# Connectors.net
KiCad netlist of a schematic drawn in Altium Designer
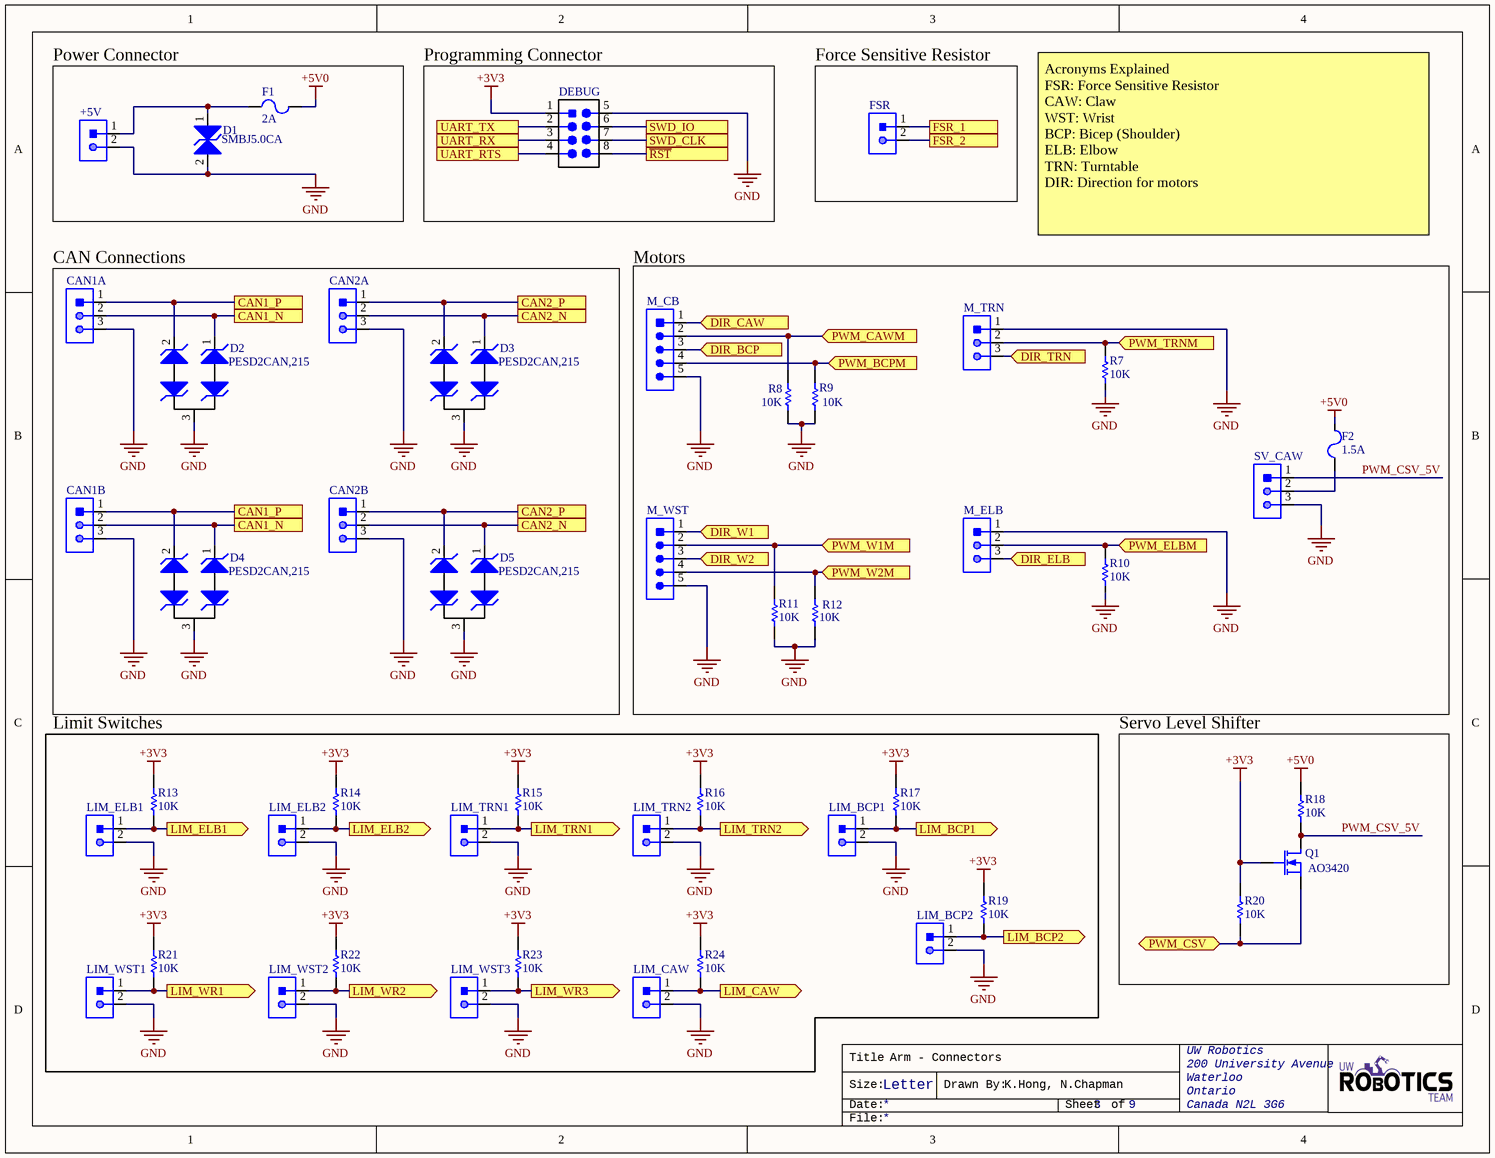
[diagram p0: Connectors.SchDoc]

(export (version "E")
  (design (tool "Eeschema 10.0.6"))
  (components
    (comp (ref "+5V")
      (value "CON_2M_SM4")
      (footprint "JST-B2B-SM4-TB")
      (description "CONN HEADER SMD 2POS 2MM")
      (fields
        (field (name "MANUFACTURER") "JST")
        (field (name "MANUFACTURER PART NUMBER") "B2B-PH-SM4-TB(LF)(SN)")
      )
      (libsource (lib "UWRT_Schematic_Library_2020") (part "CON_2M_SM4"))
    )
    (comp (ref "CAN1A")
      (value "CON_3M_SM4")
      (footprint "JST-B3B-SM4-TB")
      (description "CONN HEADER SMD 3POS 2MM")
      (fields
        (field (name "MANUFACTURER") "JST")
        (field (name "MANUFACTURER PART NUMBER") "B3B-PH-SM4-TB(LF)(SN)")
      )
      (libsource (lib "UWRT_Schematic_Library_2020") (part "CON_3M_SM4"))
    )
    (comp (ref "CAN1B")
      (value "CON_3M_SM4")
      (footprint "JST-B3B-SM4-TB")
      (description "CONN HEADER SMD 3POS 2MM")
      (fields
        (field (name "MANUFACTURER") "JST")
        (field (name "MANUFACTURER PART NUMBER") "B3B-PH-SM4-TB(LF)(SN)")
      )
      (libsource (lib "UWRT_Schematic_Library_2020") (part "CON_3M_SM4"))
    )
    (comp (ref "CAN2A")
      (value "CON_3M_SM4")
      (footprint "JST-B3B-SM4-TB")
      (description "CONN HEADER SMD 3POS 2MM")
      (fields
        (field (name "MANUFACTURER") "JST")
        (field (name "MANUFACTURER PART NUMBER") "B3B-PH-SM4-TB(LF)(SN)")
      )
      (libsource (lib "UWRT_Schematic_Library_2020") (part "CON_3M_SM4"))
    )
    (comp (ref "CAN2B")
      (value "CON_3M_SM4")
      (footprint "JST-B3B-SM4-TB")
      (description "CONN HEADER SMD 3POS 2MM")
      (fields
        (field (name "MANUFACTURER") "JST")
        (field (name "MANUFACTURER PART NUMBER") "B3B-PH-SM4-TB(LF)(SN)")
      )
      (libsource (lib "UWRT_Schematic_Library_2020") (part "CON_3M_SM4"))
    )
    (comp (ref "D1")
      (value "TVS_DIODE_BIDIRECTIONAL")
      (footprint "TVS_DIODE_BIDIRECTIONAL")
      (description "TVS DIODE 5V 9.2V DO214AA")
      (fields (field (name "MANUFACTURER PART NUMBER 1") "SMBJ5.0CA"))
      (libsource (lib "UWRT_Schematic_Library_2020") (part "TVS_DIODE_BIDIRECTIONAL"))
    )
    (comp (ref "D2")
      (value "TVS_DIODE_CAN")
      (footprint "NXP-SOT323-3")
      (description "TVS DIODE 24V 41V SOT323-3")
      (fields
        (field (name "MANUFACTURER") "Nexperia USA Inc.")
        (field (name "MANUFACTURER PART NUMBER") "PESD2CAN,215")
      )
      (libsource (lib "UWRT_Schematic_Library_2020") (part "TVS_DIODE_CAN"))
    )
    (comp (ref "D3")
      (value "TVS_DIODE_CAN")
      (footprint "NXP-SOT323-3")
      (description "TVS DIODE 24V 41V SOT323-3")
      (fields
        (field (name "MANUFACTURER") "Nexperia USA Inc.")
        (field (name "MANUFACTURER PART NUMBER") "PESD2CAN,215")
      )
      (libsource (lib "UWRT_Schematic_Library_2020") (part "TVS_DIODE_CAN"))
    )
    (comp (ref "D4")
      (value "TVS_DIODE_CAN")
      (footprint "NXP-SOT323-3")
      (description "TVS DIODE 24V 41V SOT323-3")
      (fields
        (field (name "MANUFACTURER") "Nexperia USA Inc.")
        (field (name "MANUFACTURER PART NUMBER") "PESD2CAN,215")
      )
      (libsource (lib "UWRT_Schematic_Library_2020") (part "TVS_DIODE_CAN"))
    )
    (comp (ref "D5")
      (value "TVS_DIODE_CAN")
      (footprint "NXP-SOT323-3")
      (description "TVS DIODE 24V 41V SOT323-3")
      (fields
        (field (name "MANUFACTURER") "Nexperia USA Inc.")
        (field (name "MANUFACTURER PART NUMBER") "PESD2CAN,215")
      )
      (libsource (lib "UWRT_Schematic_Library_2020") (part "TVS_DIODE_CAN"))
    )
    (comp (ref "DEBUG")
      (value "HEADER 4X2")
      (footprint "HEADER_2X4")
      (description "CONN HEADER VERT 8POS 2.54MM")
      (libsource (lib "UWRT_Schematic_Library_2020") (part "HEADER 4X2"))
    )
    (comp (ref "F1")
      (value "FUSE_2A_0603")
      (footprint "FUSE_0603")
      (description "FUSE SMD 2A 32V")
      (fields (field (name "CURRENT RATING") "2A"))
      (libsource (lib "UWRT_Schematic_Library_2020") (part "FUSE_2A_0603"))
    )
    (comp (ref "F2")
      (value "FUSE_1.5A_0603")
      (footprint "FUSE_0603")
      (description "FUSE SMD 1.5A 32V")
      (fields (field (name "CURRENT RATING") "1.5A"))
      (libsource (lib "UWRT_Schematic_Library_2020") (part "FUSE_1.5A_0603"))
    )
    (comp (ref "FSR")
      (value "CON_2M_SM4")
      (footprint "JST-B2B-SM4-TB")
      (description "CONN HEADER SMD 2POS 2MM")
      (fields
        (field (name "MANUFACTURER") "JST")
        (field (name "MANUFACTURER PART NUMBER") "B2B-PH-SM4-TB(LF)(SN)")
      )
      (libsource (lib "UWRT_Schematic_Library_2020") (part "CON_2M_SM4"))
    )
    (comp (ref "LIM_BCP1")
      (value "CON_2M_SM4")
      (footprint "JST-B2B-SM4-TB")
      (description "CONN HEADER SMD 2POS 2MM")
      (fields
        (field (name "MANUFACTURER") "JST")
        (field (name "MANUFACTURER PART NUMBER") "B2B-PH-SM4-TB(LF)(SN)")
      )
      (libsource (lib "UWRT_Schematic_Library_2020") (part "CON_2M_SM4"))
    )
    (comp (ref "LIM_BCP2")
      (value "CON_2M_SM4")
      (footprint "JST-B2B-SM4-TB")
      (description "CONN HEADER SMD 2POS 2MM")
      (fields
        (field (name "MANUFACTURER") "JST")
        (field (name "MANUFACTURER PART NUMBER") "B2B-PH-SM4-TB(LF)(SN)")
      )
      (libsource (lib "UWRT_Schematic_Library_2020") (part "CON_2M_SM4"))
    )
    (comp (ref "LIM_CAW")
      (value "CON_2M_SM4")
      (footprint "JST-B2B-SM4-TB")
      (description "CONN HEADER SMD 2POS 2MM")
      (fields
        (field (name "MANUFACTURER") "JST")
        (field (name "MANUFACTURER PART NUMBER") "B2B-PH-SM4-TB(LF)(SN)")
      )
      (libsource (lib "UWRT_Schematic_Library_2020") (part "CON_2M_SM4"))
    )
    (comp (ref "LIM_ELB1")
      (value "CON_2M_SM4")
      (footprint "JST-B2B-SM4-TB")
      (description "CONN HEADER SMD 2POS 2MM")
      (fields
        (field (name "MANUFACTURER") "JST")
        (field (name "MANUFACTURER PART NUMBER") "B2B-PH-SM4-TB(LF)(SN)")
      )
      (libsource (lib "UWRT_Schematic_Library_2020") (part "CON_2M_SM4"))
    )
    (comp (ref "LIM_ELB2")
      (value "CON_2M_SM4")
      (footprint "JST-B2B-SM4-TB")
      (description "CONN HEADER SMD 2POS 2MM")
      (fields
        (field (name "MANUFACTURER") "JST")
        (field (name "MANUFACTURER PART NUMBER") "B2B-PH-SM4-TB(LF)(SN)")
      )
      (libsource (lib "UWRT_Schematic_Library_2020") (part "CON_2M_SM4"))
    )
    (comp (ref "LIM_TRN1")
      (value "CON_2M_SM4")
      (footprint "JST-B2B-SM4-TB")
      (description "CONN HEADER SMD 2POS 2MM")
      (fields
        (field (name "MANUFACTURER") "JST")
        (field (name "MANUFACTURER PART NUMBER") "B2B-PH-SM4-TB(LF)(SN)")
      )
      (libsource (lib "UWRT_Schematic_Library_2020") (part "CON_2M_SM4"))
    )
    (comp (ref "LIM_TRN2")
      (value "CON_2M_SM4")
      (footprint "JST-B2B-SM4-TB")
      (description "CONN HEADER SMD 2POS 2MM")
      (fields
        (field (name "MANUFACTURER") "JST")
        (field (name "MANUFACTURER PART NUMBER") "B2B-PH-SM4-TB(LF)(SN)")
      )
      (libsource (lib "UWRT_Schematic_Library_2020") (part "CON_2M_SM4"))
    )
    (comp (ref "LIM_WST1")
      (value "CON_2M_SM4")
      (footprint "JST-B2B-SM4-TB")
      (description "CONN HEADER SMD 2POS 2MM")
      (fields
        (field (name "MANUFACTURER") "JST")
        (field (name "MANUFACTURER PART NUMBER") "B2B-PH-SM4-TB(LF)(SN)")
      )
      (libsource (lib "UWRT_Schematic_Library_2020") (part "CON_2M_SM4"))
    )
    (comp (ref "LIM_WST2")
      (value "CON_2M_SM4")
      (footprint "JST-B2B-SM4-TB")
      (description "CONN HEADER SMD 2POS 2MM")
      (fields
        (field (name "MANUFACTURER") "JST")
        (field (name "MANUFACTURER PART NUMBER") "B2B-PH-SM4-TB(LF)(SN)")
      )
      (libsource (lib "UWRT_Schematic_Library_2020") (part "CON_2M_SM4"))
    )
    (comp (ref "LIM_WST3")
      (value "CON_2M_SM4")
      (footprint "JST-B2B-SM4-TB")
      (description "CONN HEADER SMD 2POS 2MM")
      (fields
        (field (name "MANUFACTURER") "JST")
        (field (name "MANUFACTURER PART NUMBER") "B2B-PH-SM4-TB(LF)(SN)")
      )
      (libsource (lib "UWRT_Schematic_Library_2020") (part "CON_2M_SM4"))
    )
    (comp (ref "M_CB")
      (value "CON_5M_SM4")
      (footprint "JST-B5B-SM4-TB")
      (description "CONN HEADER SMD 5POS 2MM")
      (fields
        (field (name "MANUFACTURER") "JST")
        (field (name "MANUFACTURER PART NUMBER") "B5B-PH-SM4-TB(LF)(SN)")
      )
      (libsource (lib "UWRT_Schematic_Library_2020") (part "CON_5M_SM4"))
    )
    (comp (ref "M_ELB")
      (value "CON_3M_SM4")
      (footprint "JST-B3B-SM4-TB")
      (description "CONN HEADER SMD 3POS 2MM")
      (fields
        (field (name "MANUFACTURER") "JST")
        (field (name "MANUFACTURER PART NUMBER") "B3B-PH-SM4-TB(LF)(SN)")
      )
      (libsource (lib "UWRT_Schematic_Library_2020") (part "CON_3M_SM4"))
    )
    (comp (ref "M_TRN")
      (value "CON_3M_SM4")
      (footprint "JST-B3B-SM4-TB")
      (description "CONN HEADER SMD 3POS 2MM")
      (fields
        (field (name "MANUFACTURER") "JST")
        (field (name "MANUFACTURER PART NUMBER") "B3B-PH-SM4-TB(LF)(SN)")
      )
      (libsource (lib "UWRT_Schematic_Library_2020") (part "CON_3M_SM4"))
    )
    (comp (ref "M_WST")
      (value "CON_5M_SM4")
      (footprint "JST-B5B-SM4-TB")
      (description "CONN HEADER SMD 5POS 2MM")
      (fields
        (field (name "MANUFACTURER") "JST")
        (field (name "MANUFACTURER PART NUMBER") "B5B-PH-SM4-TB(LF)(SN)")
      )
      (libsource (lib "UWRT_Schematic_Library_2020") (part "CON_5M_SM4"))
    )
    (comp (ref "Q1")
      (value "NMOS_20V_6A")
      (footprint "NMOS_SOT23-3")
      (description "MOSFET N-CH 20V 6A SOT23")
      (fields (field (name "MPN") "AO3420") (field (name "MANUFACTURER") "Alpha & Omega"))
      (libsource (lib "UWRT_Schematic_Library_2020") (part "NMOS_20V_6A"))
    )
    (comp (ref "R7")
      (value "10K")
      (footprint "RESC0603(1608)_N")
      (description "RES SMD 10K OHM 5% 1/10W 0603")
      (fields (field (name "MANUFACTURER") "Yageo") (field (name "MPN") "RC0603JR-0710KL"))
      (libsource (lib "UWRT_Schematic_Library_2020") (part "RES_10K_0603"))
    )
    (comp (ref "R8")
      (value "10K")
      (footprint "RESC0603(1608)_N")
      (description "RES SMD 10K OHM 5% 1/10W 0603")
      (fields (field (name "MANUFACTURER") "Yageo") (field (name "MPN") "RC0603JR-0710KL"))
      (libsource (lib "UWRT_Schematic_Library_2020") (part "RES_10K_0603"))
    )
    (comp (ref "R9")
      (value "10K")
      (footprint "RESC0603(1608)_N")
      (description "RES SMD 10K OHM 5% 1/10W 0603")
      (fields (field (name "MANUFACTURER") "Yageo") (field (name "MPN") "RC0603JR-0710KL"))
      (libsource (lib "UWRT_Schematic_Library_2020") (part "RES_10K_0603"))
    )
    (comp (ref "R10")
      (value "10K")
      (footprint "RESC0603(1608)_N")
      (description "RES SMD 10K OHM 5% 1/10W 0603")
      (fields (field (name "MANUFACTURER") "Yageo") (field (name "MPN") "RC0603JR-0710KL"))
      (libsource (lib "UWRT_Schematic_Library_2020") (part "RES_10K_0603"))
    )
    (comp (ref "R11")
      (value "10K")
      (footprint "RESC0603(1608)_N")
      (description "RES SMD 10K OHM 5% 1/10W 0603")
      (fields (field (name "MANUFACTURER") "Yageo") (field (name "MPN") "RC0603JR-0710KL"))
      (libsource (lib "UWRT_Schematic_Library_2020") (part "RES_10K_0603"))
    )
    (comp (ref "R12")
      (value "10K")
      (footprint "RESC0603(1608)_N")
      (description "RES SMD 10K OHM 5% 1/10W 0603")
      (fields (field (name "MANUFACTURER") "Yageo") (field (name "MPN") "RC0603JR-0710KL"))
      (libsource (lib "UWRT_Schematic_Library_2020") (part "RES_10K_0603"))
    )
    (comp (ref "R13")
      (value "10K")
      (footprint "RESC0603(1608)_N")
      (description "RES SMD 10K OHM 5% 1/10W 0603")
      (fields (field (name "MANUFACTURER") "Yageo") (field (name "MPN") "RC0603JR-0710KL"))
      (libsource (lib "UWRT_Schematic_Library_2020") (part "RES_10K_0603"))
    )
    (comp (ref "R14")
      (value "10K")
      (footprint "RESC0603(1608)_N")
      (description "RES SMD 10K OHM 5% 1/10W 0603")
      (fields (field (name "MANUFACTURER") "Yageo") (field (name "MPN") "RC0603JR-0710KL"))
      (libsource (lib "UWRT_Schematic_Library_2020") (part "RES_10K_0603"))
    )
    (comp (ref "R15")
      (value "10K")
      (footprint "RESC0603(1608)_N")
      (description "RES SMD 10K OHM 5% 1/10W 0603")
      (fields (field (name "MANUFACTURER") "Yageo") (field (name "MPN") "RC0603JR-0710KL"))
      (libsource (lib "UWRT_Schematic_Library_2020") (part "RES_10K_0603"))
    )
    (comp (ref "R16")
      (value "10K")
      (footprint "RESC0603(1608)_N")
      (description "RES SMD 10K OHM 5% 1/10W 0603")
      (fields (field (name "MANUFACTURER") "Yageo") (field (name "MPN") "RC0603JR-0710KL"))
      (libsource (lib "UWRT_Schematic_Library_2020") (part "RES_10K_0603"))
    )
    (comp (ref "R17")
      (value "10K")
      (footprint "RESC0603(1608)_N")
      (description "RES SMD 10K OHM 5% 1/10W 0603")
      (fields (field (name "MANUFACTURER") "Yageo") (field (name "MPN") "RC0603JR-0710KL"))
      (libsource (lib "UWRT_Schematic_Library_2020") (part "RES_10K_0603"))
    )
    (comp (ref "R18")
      (value "10K")
      (footprint "RESC0603(1608)_N")
      (description "RES SMD 10K OHM 5% 1/10W 0603")
      (fields (field (name "MANUFACTURER") "Yageo") (field (name "MPN") "RC0603JR-0710KL"))
      (libsource (lib "UWRT_Schematic_Library_2020") (part "RES_10K_0603"))
    )
    (comp (ref "R19")
      (value "10K")
      (footprint "RESC0603(1608)_N")
      (description "RES SMD 10K OHM 5% 1/10W 0603")
      (fields (field (name "MANUFACTURER") "Yageo") (field (name "MPN") "RC0603JR-0710KL"))
      (libsource (lib "UWRT_Schematic_Library_2020") (part "RES_10K_0603"))
    )
    (comp (ref "R20")
      (value "10K")
      (footprint "RESC0603(1608)_N")
      (description "RES SMD 10K OHM 5% 1/10W 0603")
      (fields (field (name "MANUFACTURER") "Yageo") (field (name "MPN") "RC0603JR-0710KL"))
      (libsource (lib "UWRT_Schematic_Library_2020") (part "RES_10K_0603"))
    )
    (comp (ref "R21")
      (value "10K")
      (footprint "RESC0603(1608)_N")
      (description "RES SMD 10K OHM 5% 1/10W 0603")
      (fields (field (name "MANUFACTURER") "Yageo") (field (name "MPN") "RC0603JR-0710KL"))
      (libsource (lib "UWRT_Schematic_Library_2020") (part "RES_10K_0603"))
    )
    (comp (ref "R22")
      (value "10K")
      (footprint "RESC0603(1608)_N")
      (description "RES SMD 10K OHM 5% 1/10W 0603")
      (fields (field (name "MANUFACTURER") "Yageo") (field (name "MPN") "RC0603JR-0710KL"))
      (libsource (lib "UWRT_Schematic_Library_2020") (part "RES_10K_0603"))
    )
    (comp (ref "R23")
      (value "10K")
      (footprint "RESC0603(1608)_N")
      (description "RES SMD 10K OHM 5% 1/10W 0603")
      (fields (field (name "MANUFACTURER") "Yageo") (field (name "MPN") "RC0603JR-0710KL"))
      (libsource (lib "UWRT_Schematic_Library_2020") (part "RES_10K_0603"))
    )
    (comp (ref "R24")
      (value "10K")
      (footprint "RESC0603(1608)_N")
      (description "RES SMD 10K OHM 5% 1/10W 0603")
      (fields (field (name "MANUFACTURER") "Yageo") (field (name "MPN") "RC0603JR-0710KL"))
      (libsource (lib "UWRT_Schematic_Library_2020") (part "RES_10K_0603"))
    )
    (comp (ref "SV_CAW")
      (value "CON_3M_SM4")
      (footprint "JST-B3B-SM4-TB")
      (description "CONN HEADER SMD 3POS 2MM")
      (fields
        (field (name "MANUFACTURER") "JST")
        (field (name "MANUFACTURER PART NUMBER") "B3B-PH-SM4-TB(LF)(SN)")
      )
      (libsource (lib "UWRT_Schematic_Library_2020") (part "CON_3M_SM4"))
    )
  )
  (nets
    (net (code "1") (name "+3V3") (class "Default")
      (node (ref "DEBUG") (pin "1") (pinfunction "VCC_1") (pintype "passive"))
      (node (ref "Q1") (pin "1") (pinfunction "G_1") (pintype "passive"))
      (node (ref "R13") (pin "2") (pinfunction "2_2") (pintype "passive"))
      (node (ref "R14") (pin "2") (pinfunction "2_2") (pintype "passive"))
      (node (ref "R15") (pin "2") (pinfunction "2_2") (pintype "passive"))
      (node (ref "R16") (pin "2") (pinfunction "2_2") (pintype "passive"))
      (node (ref "R17") (pin "2") (pinfunction "2_2") (pintype "passive"))
      (node (ref "R19") (pin "2") (pinfunction "2_2") (pintype "passive"))
      (node (ref "R20") (pin "2") (pinfunction "2_2") (pintype "passive"))
      (node (ref "R21") (pin "2") (pinfunction "2_2") (pintype "passive"))
      (node (ref "R22") (pin "2") (pinfunction "2_2") (pintype "passive"))
      (node (ref "R23") (pin "2") (pinfunction "2_2") (pintype "passive"))
      (node (ref "R24") (pin "2") (pinfunction "2_2") (pintype "passive"))
    )
    (net (code "2") (name "+5V0") (class "Default")
      (node (ref "F1") (pin "2") (pinfunction "2_2") (pintype "passive"))
      (node (ref "F2") (pin "2") (pinfunction "2_2") (pintype "passive"))
      (node (ref "R18") (pin "2") (pinfunction "2_2") (pintype "passive"))
    )
    (net (code "3") (name "/CAN1_N") (class "Default")
      (node (ref "CAN1A") (pin "2") (pinfunction "2_2") (pintype "passive"))
      (node (ref "CAN1B") (pin "2") (pinfunction "2_2") (pintype "passive"))
      (node (ref "D2") (pin "1") (pinfunction "1_1") (pintype "passive"))
      (node (ref "D4") (pin "1") (pinfunction "1_1") (pintype "passive"))
    )
    (net (code "4") (name "/CAN1_P") (class "Default")
      (node (ref "CAN1A") (pin "1") (pinfunction "1_1") (pintype "passive"))
      (node (ref "CAN1B") (pin "1") (pinfunction "1_1") (pintype "passive"))
      (node (ref "D2") (pin "2") (pinfunction "2_2") (pintype "passive"))
      (node (ref "D4") (pin "2") (pinfunction "2_2") (pintype "passive"))
    )
    (net (code "5") (name "/CAN2_N") (class "Default")
      (node (ref "CAN2A") (pin "2") (pinfunction "2_2") (pintype "passive"))
      (node (ref "CAN2B") (pin "2") (pinfunction "2_2") (pintype "passive"))
      (node (ref "D3") (pin "1") (pinfunction "1_1") (pintype "passive"))
      (node (ref "D5") (pin "1") (pinfunction "1_1") (pintype "passive"))
    )
    (net (code "6") (name "/CAN2_P") (class "Default")
      (node (ref "CAN2A") (pin "1") (pinfunction "1_1") (pintype "passive"))
      (node (ref "CAN2B") (pin "1") (pinfunction "1_1") (pintype "passive"))
      (node (ref "D3") (pin "2") (pinfunction "2_2") (pintype "passive"))
      (node (ref "D5") (pin "2") (pinfunction "2_2") (pintype "passive"))
    )
    (net (code "7") (name "/DIR_BCP") (class "Default")
      (node (ref "M_CB") (pin "3") (pinfunction "3_3") (pintype "passive"))
    )
    (net (code "8") (name "/DIR_CAW") (class "Default")
      (node (ref "M_CB") (pin "1") (pinfunction "1_1") (pintype "passive"))
    )
    (net (code "9") (name "/DIR_ELB") (class "Default")
      (node (ref "M_ELB") (pin "3") (pinfunction "3_3") (pintype "passive"))
    )
    (net (code "10") (name "/DIR_TRN") (class "Default")
      (node (ref "M_TRN") (pin "3") (pinfunction "3_3") (pintype "passive"))
    )
    (net (code "11") (name "/DIR_W1") (class "Default")
      (node (ref "M_WST") (pin "1") (pinfunction "1_1") (pintype "passive"))
    )
    (net (code "12") (name "/DIR_W2") (class "Default")
      (node (ref "M_WST") (pin "3") (pinfunction "3_3") (pintype "passive"))
    )
    (net (code "13") (name "/FSR_1") (class "Default")
      (node (ref "FSR") (pin "1") (pinfunction "1_1") (pintype "passive"))
    )
    (net (code "14") (name "/FSR_2") (class "Default")
      (node (ref "FSR") (pin "2") (pinfunction "2_2") (pintype "passive"))
    )
    (net (code "15") (name "/LIM_BCP1") (class "Default")
      (node (ref "LIM_BCP1") (pin "1") (pinfunction "1_1") (pintype "passive"))
      (node (ref "R17") (pin "1") (pinfunction "1_1") (pintype "passive"))
    )
    (net (code "16") (name "/LIM_BCP2") (class "Default")
      (node (ref "LIM_BCP2") (pin "1") (pinfunction "1_1") (pintype "passive"))
      (node (ref "R19") (pin "1") (pinfunction "1_1") (pintype "passive"))
    )
    (net (code "17") (name "/LIM_CAW") (class "Default")
      (node (ref "LIM_CAW") (pin "1") (pinfunction "1_1") (pintype "passive"))
      (node (ref "R24") (pin "1") (pinfunction "1_1") (pintype "passive"))
    )
    (net (code "18") (name "/LIM_ELB1") (class "Default")
      (node (ref "LIM_ELB1") (pin "1") (pinfunction "1_1") (pintype "passive"))
      (node (ref "R13") (pin "1") (pinfunction "1_1") (pintype "passive"))
    )
    (net (code "19") (name "/LIM_ELB2") (class "Default")
      (node (ref "LIM_ELB2") (pin "1") (pinfunction "1_1") (pintype "passive"))
      (node (ref "R14") (pin "1") (pinfunction "1_1") (pintype "passive"))
    )
    (net (code "20") (name "/LIM_TRN1") (class "Default")
      (node (ref "LIM_TRN1") (pin "1") (pinfunction "1_1") (pintype "passive"))
      (node (ref "R15") (pin "1") (pinfunction "1_1") (pintype "passive"))
    )
    (net (code "21") (name "/LIM_TRN2") (class "Default")
      (node (ref "LIM_TRN2") (pin "1") (pinfunction "1_1") (pintype "passive"))
      (node (ref "R16") (pin "1") (pinfunction "1_1") (pintype "passive"))
    )
    (net (code "22") (name "/LIM_WR1") (class "Default")
      (node (ref "LIM_WST1") (pin "1") (pinfunction "1_1") (pintype "passive"))
      (node (ref "R21") (pin "1") (pinfunction "1_1") (pintype "passive"))
    )
    (net (code "23") (name "/LIM_WR2") (class "Default")
      (node (ref "LIM_WST2") (pin "1") (pinfunction "1_1") (pintype "passive"))
      (node (ref "R22") (pin "1") (pinfunction "1_1") (pintype "passive"))
    )
    (net (code "24") (name "/LIM_WR3") (class "Default")
      (node (ref "LIM_WST3") (pin "1") (pinfunction "1_1") (pintype "passive"))
      (node (ref "R23") (pin "1") (pinfunction "1_1") (pintype "passive"))
    )
    (net (code "25") (name "/PWM_BCPM") (class "Default")
      (node (ref "M_CB") (pin "4") (pinfunction "4_4") (pintype "passive"))
      (node (ref "R9") (pin "2") (pinfunction "2_2") (pintype "passive"))
    )
    (net (code "26") (name "/PWM_CAWM") (class "Default")
      (node (ref "M_CB") (pin "2") (pinfunction "2_2") (pintype "passive"))
      (node (ref "R8") (pin "2") (pinfunction "2_2") (pintype "passive"))
    )
    (net (code "27") (name "/PWM_CSV") (class "Default")
      (node (ref "Q1") (pin "2") (pinfunction "S_2") (pintype "passive"))
      (node (ref "R20") (pin "1") (pinfunction "1_1") (pintype "passive"))
    )
    (net (code "28") (name "/PWM_CSV_5V") (class "Default")
      (node (ref "Q1") (pin "3") (pinfunction "D_3") (pintype "passive"))
      (node (ref "R18") (pin "1") (pinfunction "1_1") (pintype "passive"))
      (node (ref "SV_CAW") (pin "1") (pinfunction "1_1") (pintype "passive"))
    )
    (net (code "29") (name "/PWM_ELBM") (class "Default")
      (node (ref "M_ELB") (pin "2") (pinfunction "2_2") (pintype "passive"))
      (node (ref "R10") (pin "2") (pinfunction "2_2") (pintype "passive"))
    )
    (net (code "30") (name "/PWM_TRNM") (class "Default")
      (node (ref "M_TRN") (pin "2") (pinfunction "2_2") (pintype "passive"))
      (node (ref "R7") (pin "2") (pinfunction "2_2") (pintype "passive"))
    )
    (net (code "31") (name "/PWM_W1M") (class "Default")
      (node (ref "M_WST") (pin "2") (pinfunction "2_2") (pintype "passive"))
      (node (ref "R11") (pin "2") (pinfunction "2_2") (pintype "passive"))
    )
    (net (code "32") (name "/PWM_W2M") (class "Default")
      (node (ref "M_WST") (pin "4") (pinfunction "4_4") (pintype "passive"))
      (node (ref "R12") (pin "2") (pinfunction "2_2") (pintype "passive"))
    )
    (net (code "33") (name "/SWD_CLK") (class "Default")
      (node (ref "DEBUG") (pin "7") (pinfunction "3_7") (pintype "passive"))
    )
    (net (code "34") (name "/SWD_IO") (class "Default")
      (node (ref "DEBUG") (pin "6") (pinfunction "2_6") (pintype "passive"))
    )
    (net (code "35") (name "/UART_RTS") (class "Default")
      (node (ref "DEBUG") (pin "4") (pinfunction "4_4") (pintype "passive"))
    )
    (net (code "36") (name "/UART_RX") (class "Default")
      (node (ref "DEBUG") (pin "3") (pinfunction "3_3") (pintype "passive"))
    )
    (net (code "37") (name "/UART_TX") (class "Default")
      (node (ref "DEBUG") (pin "2") (pinfunction "2_2") (pintype "passive"))
    )
    (net (code "38") (name "/~{RST}") (class "Default")
      (node (ref "DEBUG") (pin "8") (pinfunction "4_8") (pintype "passive"))
    )
    (net (code "39") (name "GND") (class "Default")
      (node (ref "+5V") (pin "2") (pinfunction "2_2") (pintype "passive"))
      (node (ref "CAN1A") (pin "3") (pinfunction "3_3") (pintype "passive"))
      (node (ref "CAN1B") (pin "3") (pinfunction "3_3") (pintype "passive"))
      (node (ref "CAN2A") (pin "3") (pinfunction "3_3") (pintype "passive"))
      (node (ref "CAN2B") (pin "3") (pinfunction "3_3") (pintype "passive"))
      (node (ref "D1") (pin "2") (pinfunction "2_2") (pintype "passive"))
      (node (ref "D2") (pin "3") (pinfunction "3_3") (pintype "passive"))
      (node (ref "D3") (pin "3") (pinfunction "3_3") (pintype "passive"))
      (node (ref "D4") (pin "3") (pinfunction "3_3") (pintype "passive"))
      (node (ref "D5") (pin "3") (pinfunction "3_3") (pintype "passive"))
      (node (ref "DEBUG") (pin "5") (pinfunction "GND_5") (pintype "passive"))
      (node (ref "LIM_BCP1") (pin "2") (pinfunction "2_2") (pintype "passive"))
      (node (ref "LIM_BCP2") (pin "2") (pinfunction "2_2") (pintype "passive"))
      (node (ref "LIM_CAW") (pin "2") (pinfunction "2_2") (pintype "passive"))
      (node (ref "LIM_ELB1") (pin "2") (pinfunction "2_2") (pintype "passive"))
      (node (ref "LIM_ELB2") (pin "2") (pinfunction "2_2") (pintype "passive"))
      (node (ref "LIM_TRN1") (pin "2") (pinfunction "2_2") (pintype "passive"))
      (node (ref "LIM_TRN2") (pin "2") (pinfunction "2_2") (pintype "passive"))
      (node (ref "LIM_WST1") (pin "2") (pinfunction "2_2") (pintype "passive"))
      (node (ref "LIM_WST2") (pin "2") (pinfunction "2_2") (pintype "passive"))
      (node (ref "LIM_WST3") (pin "2") (pinfunction "2_2") (pintype "passive"))
      (node (ref "M_CB") (pin "5") (pinfunction "5_5") (pintype "passive"))
      (node (ref "M_ELB") (pin "1") (pinfunction "1_1") (pintype "passive"))
      (node (ref "M_TRN") (pin "1") (pinfunction "1_1") (pintype "passive"))
      (node (ref "M_WST") (pin "5") (pinfunction "5_5") (pintype "passive"))
      (node (ref "R10") (pin "1") (pinfunction "1_1") (pintype "passive"))
      (node (ref "R11") (pin "1") (pinfunction "1_1") (pintype "passive"))
      (node (ref "R12") (pin "1") (pinfunction "1_1") (pintype "passive"))
      (node (ref "R7") (pin "1") (pinfunction "1_1") (pintype "passive"))
      (node (ref "R8") (pin "1") (pinfunction "1_1") (pintype "passive"))
      (node (ref "R9") (pin "1") (pinfunction "1_1") (pintype "passive"))
      (node (ref "SV_CAW") (pin "3") (pinfunction "3_3") (pintype "passive"))
    )
    (net (code "40") (name "Net-(+5V-Pad1)") (class "Default")
      (node (ref "+5V") (pin "1") (pinfunction "1_1") (pintype "passive"))
      (node (ref "D1") (pin "1") (pinfunction "1_1") (pintype "passive"))
      (node (ref "F1") (pin "1") (pinfunction "1_1") (pintype "passive"))
    )
    (net (code "41") (name "Net-(F2-Pad1)") (class "Default")
      (node (ref "F2") (pin "1") (pinfunction "1_1") (pintype "passive"))
      (node (ref "SV_CAW") (pin "2") (pinfunction "2_2") (pintype "passive"))
    )
  )
)
